# power.net
KiCad netlist of a schematic drawn in Altium Designer
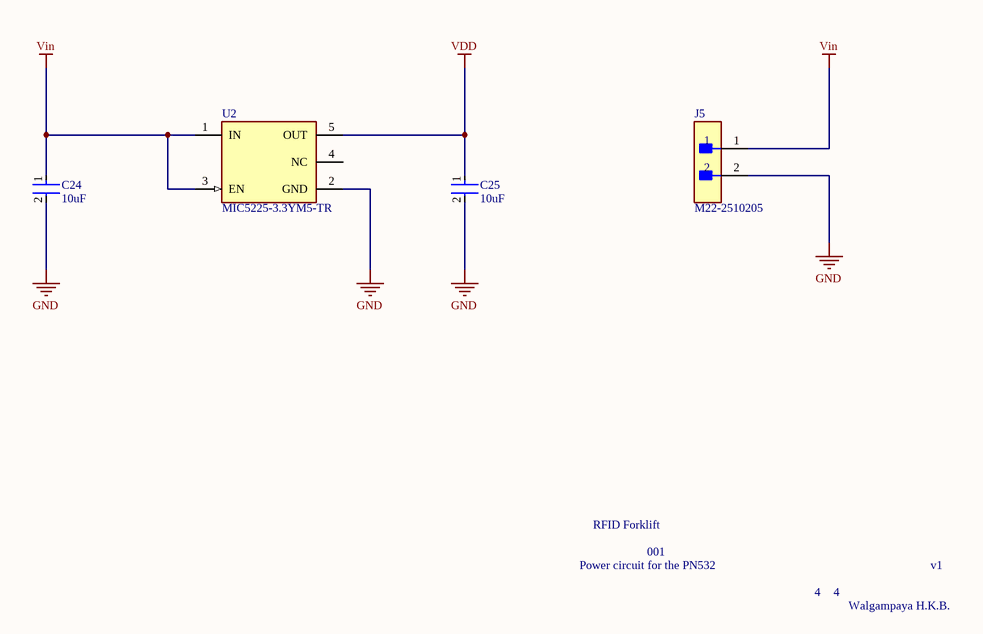
[diagram p0: power.SchDoc]

(export (version "E")
  (design (tool "Eeschema 10.0.6"))
  (components
    (comp (ref "C24")
      (value "10uF")
      (footprint "FP-CC1206-0_3-1_45-IPC_C")
      (description "CAP CER 1000PF 2KV X7R 1206")
      (fields (field (name "TOLERANCE") "10%") (field (name "VOLTAGE") "2kV"))
      (libsource (lib "Altium Content Vault") (part "02cd4be3c70576c341d710602a673aa"))
    )
    (comp (ref "C25")
      (value "10uF")
      (footprint "FP-CC1206-0_3-1_45-IPC_C")
      (description "CAP CER 1000PF 2KV X7R 1206")
      (fields (field (name "TOLERANCE") "10%") (field (name "VOLTAGE") "2kV"))
      (libsource (lib "Altium Content Vault") (part "02cd4be3c70576c341d710602a673aa"))
    )
    (comp (ref "J5")
      (value "M22-2510205")
      (footprint "FP-M22-2510205-MFG")
      (description "CONN HEADER VERT 2POS 2MM")
      (fields
        (field (name "MANUFACTURER") "Harwin")
        (field (name "OCTOPART") "https://octopart.com/m22-2510205-harwin-2538221")
      )
      (libsource (lib "Altium Content Vault") (part "3bc925449376181038e59eaffc5286c"))
    )
    (comp (ref "U2")
      (value "MIC5225-3.3YM5-TR")
      (footprint "FP-SOT23-5LD-PL-1-MFG")
      (description "IC REG LINEAR 3.3V 150MA SOT23-5")
      (fields
        (field (name "MANUFACTURER") "Microchip Technology")
        (field (name "OCTOPART") "https://octopart.com/mic5225-3.3ym5-tr-microchip-66802280")
      )
      (libsource (lib "Altium Content Vault") (part "19d222bb1c978341ac53d4d0acc2020"))
    )
  )
  (nets
    (net (code "1") (name "GND") (class "Default")
      (node (ref "C24") (pin "2") (pinfunction "2_2") (pintype "passive"))
      (node (ref "C25") (pin "2") (pinfunction "2_2") (pintype "passive"))
      (node (ref "J5") (pin "2") (pinfunction "2_2") (pintype "passive"))
      (node (ref "U2") (pin "2") (pinfunction "GND_2") (pintype "power_in"))
    )
    (net (code "2") (name "VDD") (class "Default")
      (node (ref "C25") (pin "1") (pinfunction "1_1") (pintype "passive"))
      (node (ref "U2") (pin "5") (pinfunction "OUT_5") (pintype "power_in"))
    )
    (net (code "3") (name "Vin") (class "Default")
      (node (ref "C24") (pin "1") (pinfunction "1_1") (pintype "passive"))
      (node (ref "J5") (pin "1") (pinfunction "1_1") (pintype "passive"))
      (node (ref "U2") (pin "1") (pinfunction "IN_1") (pintype "power_in"))
      (node (ref "U2") (pin "3") (pinfunction "EN_3") (pintype "input"))
    )
    (net (code "4") (name "unconnected-(U2-NC-Pad4)") (class "Default")
      (node (ref "U2") (pin "4") (pinfunction "NC_4") (pintype "passive"))
    )
  )
)
